# LM3404HV_Circuit.net
KiCad netlist of a schematic drawn in Altium Designer
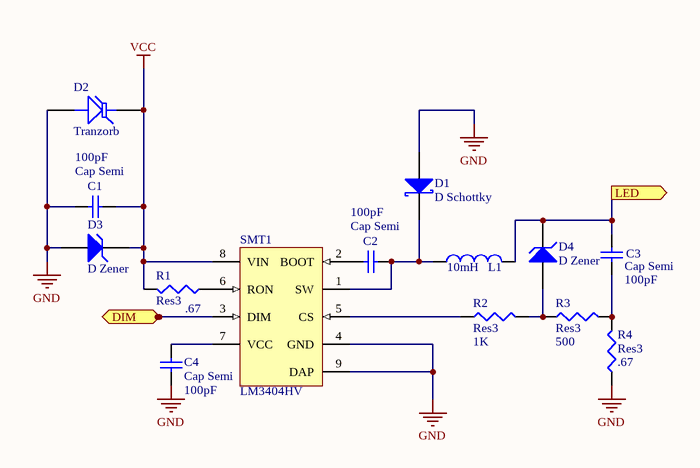
[diagram p0: LM3404HV_Circuit.SchDoc]

(export (version "E")
  (design (tool "Eeschema 10.0.6"))
  (components
    (comp (ref "C1")
      (value "Cap Semi")
      (footprint "1608[0603]")
      (description "Capacitor (Semiconductor SIM Model)")
      (fields (field (name "ALTIUM_VALUE") "100pF") (field (name "PUBLISHER") "Altium Limited"))
      (libsource (lib "Miscellaneous Devices") (part "Cap Semi"))
    )
    (comp (ref "C2")
      (value "Cap Semi")
      (footprint "1608[0603]")
      (description "Capacitor (Semiconductor SIM Model)")
      (fields (field (name "ALTIUM_VALUE") "100pF") (field (name "PUBLISHER") "Altium Limited"))
      (libsource (lib "Miscellaneous Devices") (part "Cap Semi"))
    )
    (comp (ref "C3")
      (value "Cap Semi")
      (footprint "1608[0603]")
      (description "Capacitor (Semiconductor SIM Model)")
      (fields (field (name "ALTIUM_VALUE") "100pF") (field (name "PUBLISHER") "Altium Limited"))
      (libsource (lib "Miscellaneous Devices") (part "Cap Semi"))
    )
    (comp (ref "C4")
      (value "Cap Semi")
      (footprint "1608[0603]")
      (description "Capacitor (Semiconductor SIM Model)")
      (fields (field (name "ALTIUM_VALUE") "100pF") (field (name "PUBLISHER") "Altium Limited"))
      (libsource (lib "Miscellaneous Devices") (part "Cap Semi"))
    )
    (comp (ref "D1")
      (value "D Schottky")
      (footprint "DIODE-0.4")
      (description "Schottky Diode")
      (fields (field (name "PUBLISHER") "Altium Limited"))
      (libsource (lib "Miscellaneous Devices") (part "D Schottky"))
    )
    (comp (ref "D2")
      (value "Tranzorb")
      (footprint "DO-7")
      (description "Transient Voltage Suppression (TVS) Diode")
      (fields (field (name "PUBLISHER") "Altium Limited"))
      (libsource (lib "Miscellaneous Devices") (part "Tranzorb"))
    )
    (comp (ref "D3")
      (value "D Zener")
      (footprint "DIODE-0.7")
      (description "Zener Diode")
      (fields (field (name "PUBLISHER") "Altium Limited"))
      (libsource (lib "Miscellaneous Devices") (part "D Zener"))
    )
    (comp (ref "D4")
      (value "D Zener")
      (footprint "DIODE-0.7")
      (description "Zener Diode")
      (fields (field (name "PUBLISHER") "Altium Limited"))
      (libsource (lib "Miscellaneous Devices") (part "D Zener"))
    )
    (comp (ref "L1")
      (value "10mH")
      (footprint "0603")
      (description "Inductor")
      (fields (field (name "PUBLISHER") "Altium Limited"))
      (libsource (lib "Miscellaneous Devices") (part "Inductor"))
    )
    (comp (ref "R1")
      (value "Res3")
      (footprint "J1-0603")
      (description "Resistor")
      (fields (field (name "ALTIUM_VALUE") ".67") (field (name "PUBLISHER") "Altium Limited"))
      (libsource (lib "Miscellaneous Devices") (part "Res3"))
    )
    (comp (ref "R2")
      (value "Res3")
      (footprint "J1-0603")
      (description "Resistor")
      (fields (field (name "ALTIUM_VALUE") "1K") (field (name "PUBLISHER") "Altium Limited"))
      (libsource (lib "Miscellaneous Devices") (part "Res3"))
    )
    (comp (ref "R3")
      (value "Res3")
      (footprint "J1-0603")
      (description "Resistor")
      (fields (field (name "ALTIUM_VALUE") "500") (field (name "PUBLISHER") "Altium Limited"))
      (libsource (lib "Miscellaneous Devices") (part "Res3"))
    )
    (comp (ref "R4")
      (value "Res3")
      (footprint "J1-0603")
      (description "Resistor")
      (fields (field (name "ALTIUM_VALUE") ".67") (field (name "PUBLISHER") "Altium Limited"))
      (libsource (lib "Miscellaneous Devices") (part "Res3"))
    )
    (comp (ref "SMT1")
      (value "LM3404HV")
      (footprint "MRA08B_M")
      (description "1.0A Constant Current Buck Regulator for High Power LED Drivers, 8-pin PSOP, Pb-Free")
      (fields
        (field (name "PARTNUMBER") "LM3404HVMR/NOPB")
        (field (name "MANUFACTURER") "National Semiconductor")
        (field (name "PUBLISHER") "Altium Limited")
      )
      (libsource (lib "NSC MiscPower") (part "LM3404HVMR/NOPB"))
    )
  )
  (nets
    (net (code "1") (name "/DIM") (class "Default")
      (node (ref "SMT1") (pin "3") (pinfunction "DIM_3") (pintype "input"))
    )
    (net (code "2") (name "/LED") (class "Default")
      (node (ref "C3") (pin "2") (pinfunction "2_2") (pintype "passive"))
      (node (ref "D4") (pin "2") (pinfunction "K_2") (pintype "passive"))
      (node (ref "L1") (pin "2") (pinfunction "2_2") (pintype "passive"))
    )
    (net (code "3") (name "GND") (class "Default")
      (node (ref "C1") (pin "1") (pinfunction "1_1") (pintype "passive"))
      (node (ref "C4") (pin "1") (pinfunction "1_1") (pintype "passive"))
      (node (ref "D1") (pin "1") (pinfunction "A_1") (pintype "passive"))
      (node (ref "D2") (pin "1") (pinfunction "A_1") (pintype "passive"))
      (node (ref "D3") (pin "1") (pinfunction "A_1") (pintype "passive"))
      (node (ref "R4") (pin "1") (pinfunction "1_1") (pintype "passive"))
      (node (ref "SMT1") (pin "4") (pinfunction "GND_4") (pintype "power_in"))
      (node (ref "SMT1") (pin "9") (pinfunction "DAP_9") (pintype "power_in"))
    )
    (net (code "4") (name "Net-(C3-Pad1)") (class "Default")
      (node (ref "C3") (pin "1") (pinfunction "1_1") (pintype "passive"))
      (node (ref "R3") (pin "2") (pinfunction "2_2") (pintype "passive"))
      (node (ref "R4") (pin "2") (pinfunction "2_2") (pintype "passive"))
    )
    (net (code "5") (name "Net-(D1-K)") (class "Default")
      (node (ref "C2") (pin "2") (pinfunction "2_2") (pintype "passive"))
      (node (ref "D1") (pin "2") (pinfunction "K_2") (pintype "passive"))
      (node (ref "L1") (pin "1") (pinfunction "1_1") (pintype "passive"))
      (node (ref "SMT1") (pin "1") (pinfunction "SW_1") (pintype "power_in"))
    )
    (net (code "6") (name "Net-(D4-A)") (class "Default")
      (node (ref "D4") (pin "1") (pinfunction "A_1") (pintype "passive"))
      (node (ref "R2") (pin "2") (pinfunction "2_2") (pintype "passive"))
      (node (ref "R3") (pin "1") (pinfunction "1_1") (pintype "passive"))
    )
    (net (code "7") (name "Net-(SMT1-BOOT)") (class "Default")
      (node (ref "C2") (pin "1") (pinfunction "1_1") (pintype "passive"))
      (node (ref "SMT1") (pin "2") (pinfunction "BOOT_2") (pintype "input"))
    )
    (net (code "8") (name "Net-(SMT1-CS)") (class "Default")
      (node (ref "R2") (pin "1") (pinfunction "1_1") (pintype "passive"))
      (node (ref "SMT1") (pin "5") (pinfunction "CS_5") (pintype "input"))
    )
    (net (code "9") (name "Net-(SMT1-RON)") (class "Default")
      (node (ref "R1") (pin "1") (pinfunction "1_1") (pintype "passive"))
      (node (ref "SMT1") (pin "6") (pinfunction "RON_6") (pintype "input"))
    )
    (net (code "10") (name "Net-(SMT1-VCC)") (class "Default")
      (node (ref "C4") (pin "2") (pinfunction "2_2") (pintype "passive"))
      (node (ref "SMT1") (pin "7") (pinfunction "VCC_7") (pintype "power_in"))
    )
    (net (code "11") (name "VCC") (class "Default")
      (node (ref "C1") (pin "2") (pinfunction "2_2") (pintype "passive"))
      (node (ref "D2") (pin "2") (pinfunction "K_2") (pintype "passive"))
      (node (ref "D3") (pin "2") (pinfunction "K_2") (pintype "passive"))
      (node (ref "R1") (pin "2") (pinfunction "2_2") (pintype "passive"))
      (node (ref "SMT1") (pin "8") (pinfunction "VIN_8") (pintype "power_in"))
    )
  )
)
